# NAPaC.net
KiCad netlist of a schematic drawn in Altium Designer
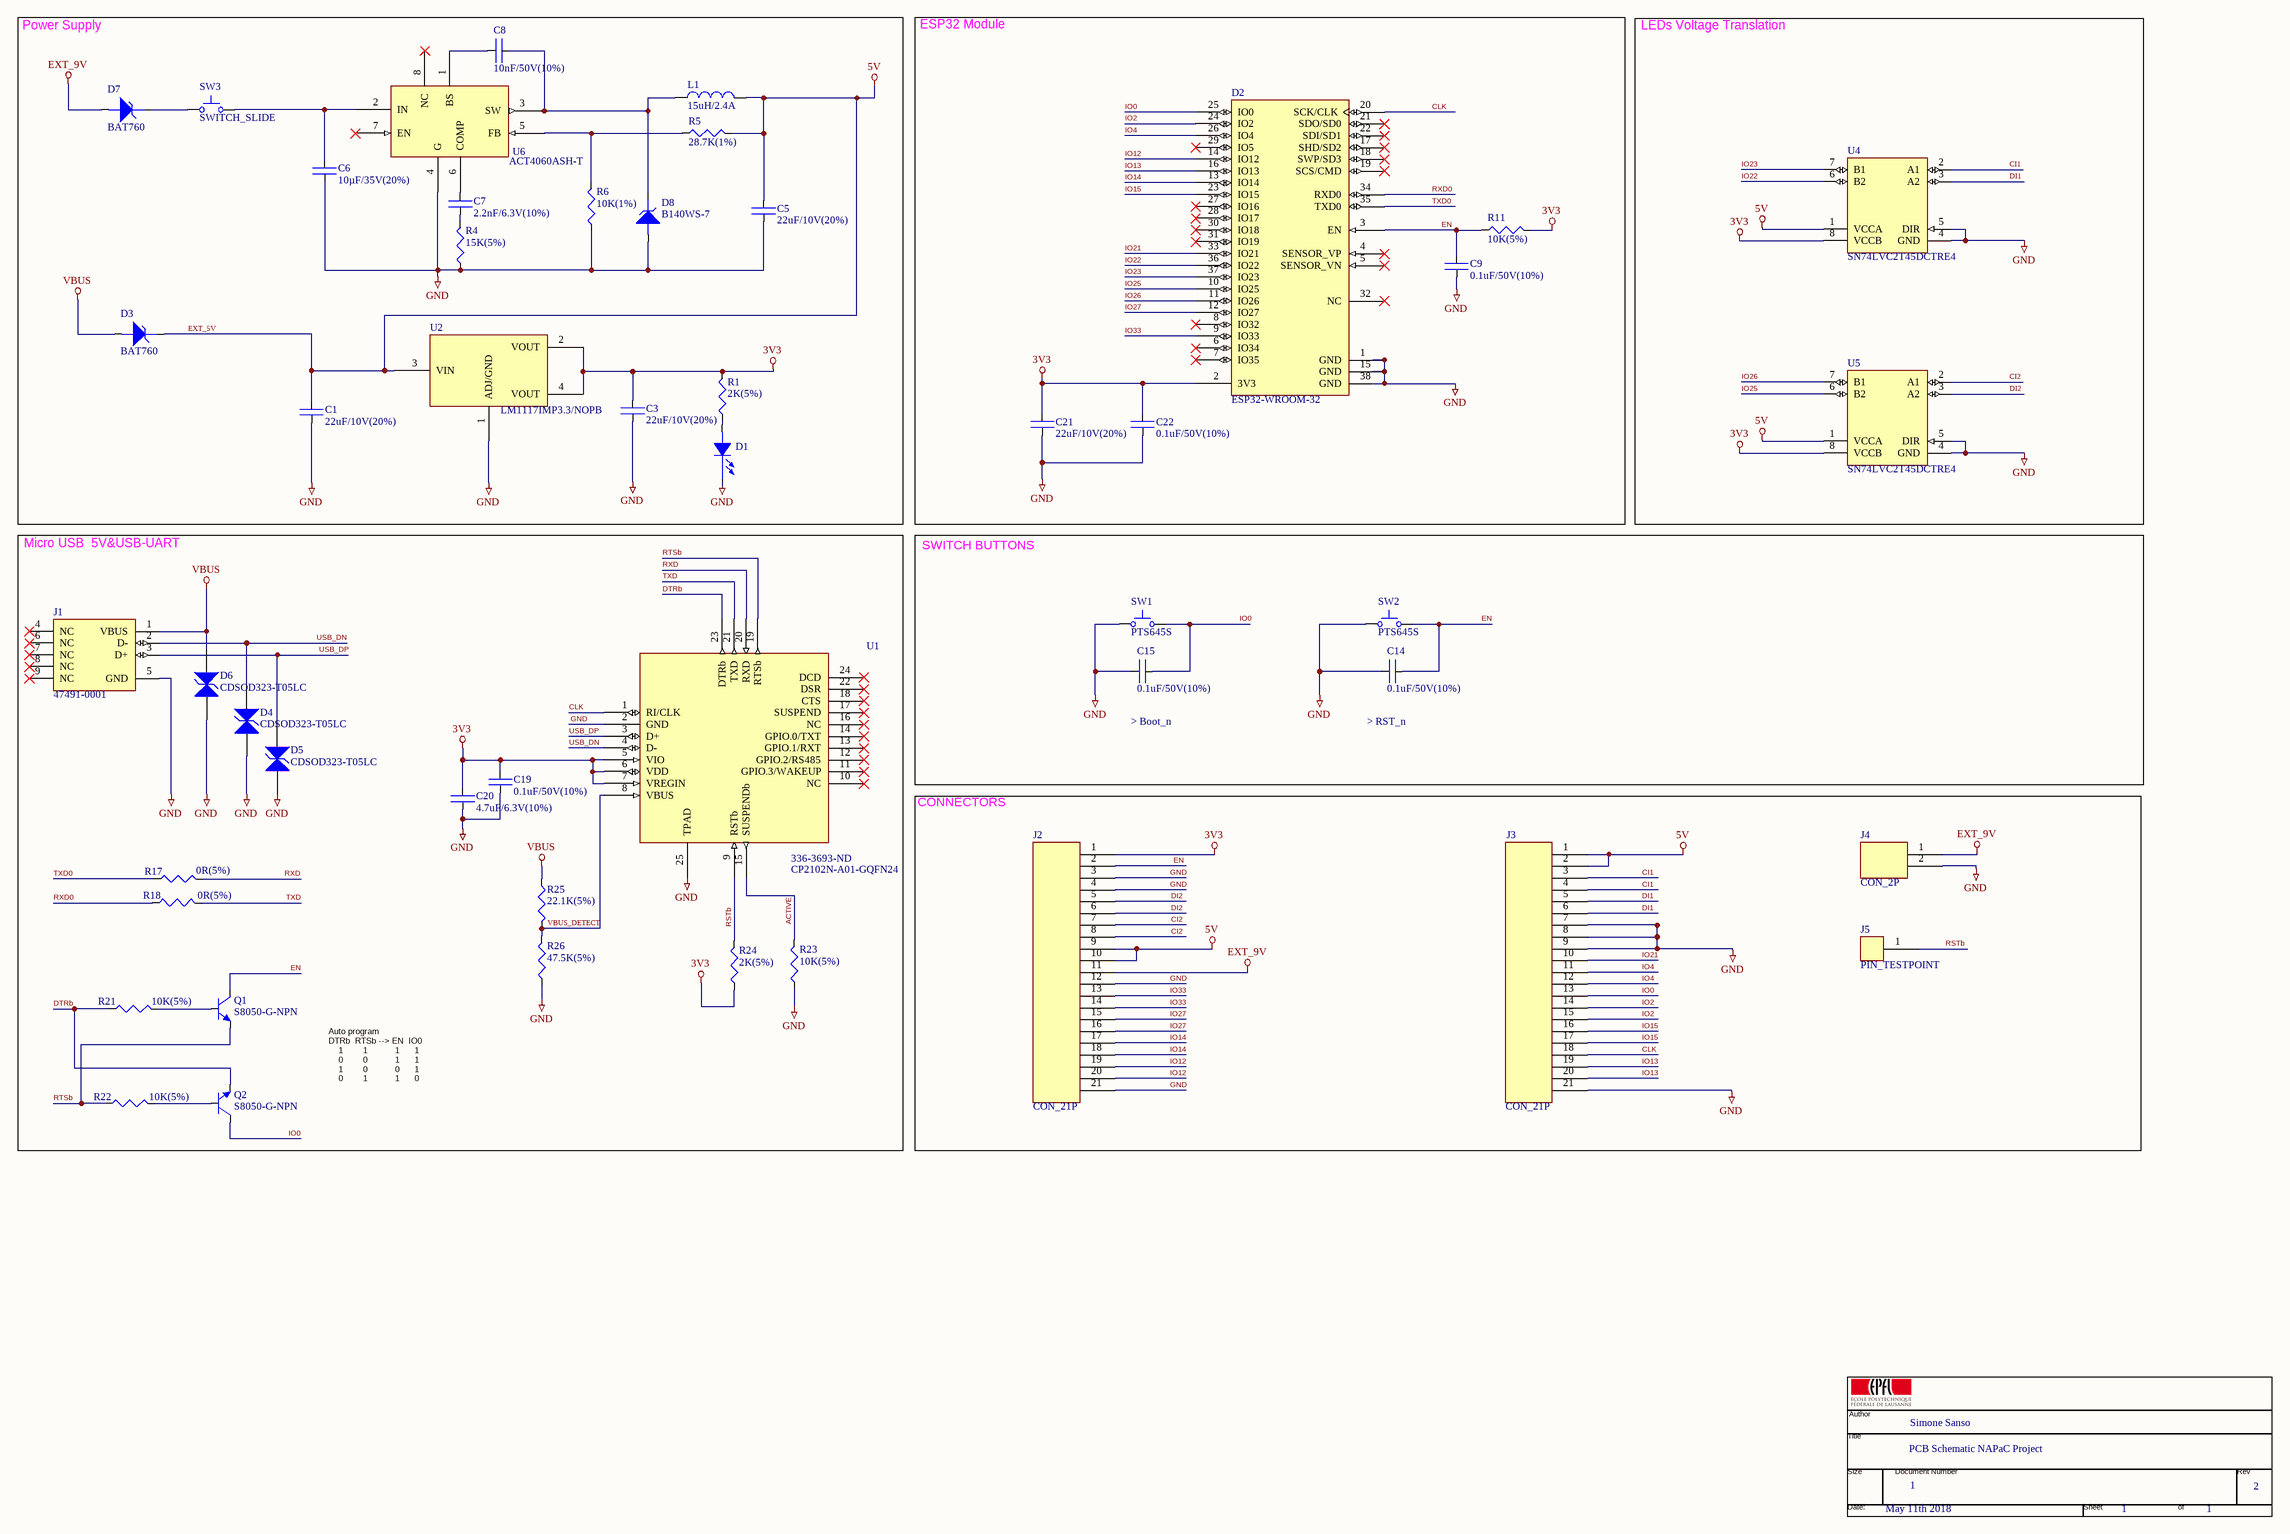
[diagram p0: NAPaC.SchDoc]

(export (version "E")
  (design (tool "Eeschema 10.0.6"))
  (components
    (comp (ref "*") (value "TITLE_BLOCK") (libsource (lib "NAPaC_Schlib") (part "TITLE_BLOCK")))
    (comp (ref "C1")
      (value "22uF/10V(20%)")
      (footprint "CAPC0603")
      (description "GRM188R61A226ME15D-22uF/10V(20%)")
      (libsource (lib "NAPaC_Schlib") (part "CAP-22uF/10V(20%)"))
    )
    (comp (ref "C3")
      (value "22uF/10V(20%)")
      (footprint "CAPC0603")
      (description "GRM188R61A226ME15D-22uF/10V(20%)")
      (libsource (lib "NAPaC_Schlib") (part "CAP-22uF/10V(20%)"))
    )
    (comp (ref "C5")
      (value "22uF/10V(20%)")
      (footprint "CAPC0603")
      (description "GRM188R61A226ME15D-22uF/10V(20%)")
      (libsource (lib "NAPaC_Schlib") (part "CAP-22uF/10V(20%)"))
    )
    (comp (ref "C6")
      (value "10µF/35V(20%)")
      (footprint "CAPC0603")
      (description "C0603C106M8PACTU")
      (libsource (lib "NAPaC_Schlib") (part "CAP-10µF/35V(20%)"))
    )
    (comp (ref "C7")
      (value "2.2nF/6.3V(10%)")
      (footprint "CAPC0603")
      (description "C0603X7R0J222K030BA")
      (libsource (lib "NAPaC_Schlib") (part "CAP-2.2nF/6.3V(10%)"))
    )
    (comp (ref "C8")
      (value "10nF/50V(10%)")
      (footprint "CAPC0603")
      (description "C1608X7R1H103K080AE")
      (libsource (lib "NAPaC_Schlib") (part "CAP-10nF/50V(10%)"))
    )
    (comp (ref "C9")
      (value "0.1uF/50V(10%)")
      (footprint "CAPC0603")
      (description "GRM188R71H104KA93D-0.1uF/50V(10%)")
      (libsource (lib "NAPaC_Schlib") (part "CAP-0.1uF/50V(10%)"))
    )
    (comp (ref "C14")
      (value "0.1uF/50V(10%)")
      (footprint "CAPC0603")
      (description "GRM188R71H104KA93D-0.1uF/50V(10%)")
      (libsource (lib "NAPaC_Schlib") (part "CAP-0.1uF/50V(10%)"))
    )
    (comp (ref "C15")
      (value "0.1uF/50V(10%)")
      (footprint "CAPC0603")
      (description "GRM188R71H104KA93D-0.1uF/50V(10%)")
      (libsource (lib "NAPaC_Schlib") (part "CAP-0.1uF/50V(10%)"))
    )
    (comp (ref "C19")
      (value "0.1uF/50V(10%)")
      (footprint "CAPC0603")
      (description "GRM188R71H104KA93D-0.1uF/50V(10%)")
      (libsource (lib "NAPaC_Schlib") (part "CAP-0.1uF/50V(10%)"))
    )
    (comp (ref "C20")
      (value "4.7uF/6.3V(10%)")
      (footprint "CAPC0603")
      (description "GRT188C80J475KE01D")
      (libsource (lib "NAPaC_Schlib") (part "CAP-0.4uF/6.3V(10%)"))
    )
    (comp (ref "C21")
      (value "22uF/10V(20%)")
      (footprint "CAPC0603")
      (description "GRM188R61A226ME15D-22uF/10V(20%)")
      (libsource (lib "NAPaC_Schlib") (part "CAP-22uF/10V(20%)"))
    )
    (comp (ref "C22")
      (value "0.1uF/50V(10%)")
      (footprint "CAPC0603")
      (description "GRM188R71H104KA93D-0.1uF/50V(10%)")
      (libsource (lib "NAPaC_Schlib") (part "CAP-0.1uF/50V(10%)"))
    )
    (comp (ref "D1")
      (value "SML-D12U1WT86")
      (footprint "SML-D12U1WT86")
      (description "SML-D12U1WT86-2.2V-20mA")
      (libsource (lib "NAPaC_Schlib") (part "RED_LED"))
    )
    (comp (ref "D2")
      (value "ESP32-WROOM-32")
      (footprint "OLMX-ESP-WROOM-32")
      (libsource (lib "NAPaC_Schlib") (part "ESP-WROOM-32"))
    )
    (comp (ref "D3")
      (value "BAT760")
      (footprint "SOD-323")
      (description "BAT760-7-Schottky Diodes & Rectifiers 0.5A 30V LF")
      (libsource (lib "NAPaC_Schlib") (part "SchottkyDiode"))
    )
    (comp (ref "D4")
      (value "CDSOD323-T05LC")
      (footprint "SOD-323")
      (libsource (lib "NAPaC_Schlib") (part "BidirectionalDiode"))
    )
    (comp (ref "D5")
      (value "CDSOD323-T05LC")
      (footprint "SOD-323")
      (libsource (lib "NAPaC_Schlib") (part "BidirectionalDiode"))
    )
    (comp (ref "D6")
      (value "CDSOD323-T05LC")
      (footprint "SOD-323")
      (libsource (lib "NAPaC_Schlib") (part "BidirectionalDiode"))
    )
    (comp (ref "D7")
      (value "BAT760")
      (footprint "SOD-323")
      (description "BAT760-7-Schottky Diodes & Rectifiers 0.5A 30V LF")
      (libsource (lib "NAPaC_Schlib") (part "SchottkyDiode"))
    )
    (comp (ref "D8")
      (value "B140WS-7")
      (footprint "SOD-323-SCHOTTKY_DIODE-40V/1A")
      (description "Diode Schottky 40V 1A 2-Pin SOD-323 T/R")
      (libsource (lib "NAPaC_Schlib") (part "SCHOTTKY_DIODE-40V/3A"))
    )
    (comp (ref "J1")
      (value "47491-0001")
      (footprint "USB-MICRO-B_V")
      (description "USB Connectors MICRO USB B RECPT MIDDLE MNT ASSY")
      (libsource (lib "NAPaC_Schlib") (part "USB_CON8"))
    )
    (comp (ref "J2")
      (value "CON_21P")
      (footprint "PINS_HEADER-21")
      (description "21 Positions Header, Breakaway Connector 0.100\" (2.54mm) Through Hole Tin")
      (libsource (lib "NAPaC_Schlib") (part "PINS_HEADER"))
    )
    (comp (ref "J3")
      (value "CON_21P")
      (footprint "PINS_HEADER-21")
      (description "21 Positions Header, Breakaway Connector 0.100\" (2.54mm) Through Hole Tin")
      (libsource (lib "NAPaC_Schlib") (part "PINS_HEADER"))
    )
    (comp (ref "J4")
      (value "CON_2P")
      (footprint "PINS_ALIM-2")
      (description "2 Positions Header, Breakaway Connector 0.100\" (2.54mm) Through Hole Tin")
      (libsource (lib "NAPaC_Schlib") (part "PIN_ALIM"))
    )
    (comp (ref "J5")
      (value "PIN_TESTPOINT")
      (footprint "PIN_TESTPOINT")
      (description "1 Position Header, Breakaway Connector 0.100\" (2.54mm) Through Hole Tin")
      (libsource (lib "NAPaC_Schlib") (part "PIN_TESTPOINT"))
    )
    (comp (ref "L1")
      (value "15uH/2.4A")
      (footprint "NRS8040-SELF-15uH/2.4A")
      (description "NRS8040T150MJGJ")
      (libsource (lib "NAPaC_Schlib") (part "SELF-15uH/2.4A"))
    )
    (comp (ref "Q1")
      (value "S8050-G-NPN")
      (footprint "SOT23")
      (description "750-SS8050-G-BJT NPN SOT-23-3 TRANSISTOR 1.5A 40V")
      (libsource (lib "NAPaC_Schlib") (part "SS8050-G-NPN"))
    )
    (comp (ref "Q2")
      (value "S8050-G-NPN")
      (description "750-SS8050-G-BJT NPN SOT-23-3 TRANSISTOR 1.5A 40V")
      (libsource (lib "NAPaC_Schlib") (part "SS8050-G-NPNbis"))
    )
    (comp (ref "R1")
      (value "2K(5%)")
      (footprint "RC0402")
      (description "RC0402JR-072KL")
      (libsource (lib "NAPaC_Schlib") (part "RESISTOR-2K(5%)"))
    )
    (comp (ref "R4")
      (value "15K(5%)")
      (footprint "RC0402")
      (description "RC0402JR-0715KL")
      (libsource (lib "NAPaC_Schlib") (part "RESISTOR-15K(5%)"))
    )
    (comp (ref "R5")
      (value "28.7K(1%)")
      (footprint "RC0402")
      (description "RC0402JR-072K7L")
      (libsource (lib "NAPaC_Schlib") (part "RESISTOR-28.7K(1%)"))
    )
    (comp (ref "R6")
      (value "10K(1%)")
      (footprint "RC0402")
      (description "RC0402F103CS")
      (libsource (lib "NAPaC_Schlib") (part "RESISTOR-10K(1%)"))
    )
    (comp (ref "R11")
      (value "10K(5%)")
      (footprint "RC0402")
      (description "RC0402JR-0710KL")
      (libsource (lib "NAPaC_Schlib") (part "RESISTOR-10K(5%)"))
    )
    (comp (ref "R17")
      (value "0R(5%)")
      (footprint "RC0402")
      (description "RC0402JR-070RL")
      (libsource (lib "NAPaC_Schlib") (part "RESISTOR-0R(5%)"))
    )
    (comp (ref "R18")
      (value "0R(5%)")
      (footprint "RC0402")
      (description "RC0402JR-070RL")
      (libsource (lib "NAPaC_Schlib") (part "RESISTOR-0R(5%)"))
    )
    (comp (ref "R21")
      (value "10K(5%)")
      (footprint "RC0402")
      (description "RC0402JR-0710KL")
      (libsource (lib "NAPaC_Schlib") (part "RESISTOR-10K(5%)"))
    )
    (comp (ref "R22")
      (value "10K(5%)")
      (footprint "RC0402")
      (description "RC0402JR-0710KL")
      (libsource (lib "NAPaC_Schlib") (part "RESISTOR-10K(5%)"))
    )
    (comp (ref "R23")
      (value "10K(5%)")
      (footprint "RC0402")
      (description "RC0402JR-0710KL")
      (libsource (lib "NAPaC_Schlib") (part "RESISTOR-10K(5%)"))
    )
    (comp (ref "R24")
      (value "2K(5%)")
      (footprint "RC0402")
      (description "RC0402JR-072KL")
      (libsource (lib "NAPaC_Schlib") (part "RESISTOR-2K(5%)"))
    )
    (comp (ref "R25")
      (value "22.1K(5%)")
      (footprint "RC0402")
      (description "RC0402FR-0722K1L")
      (libsource (lib "NAPaC_Schlib") (part "RESISTOR-22.1K(5%)"))
    )
    (comp (ref "R26")
      (value "47.5K(5%)")
      (footprint "RC0402")
      (description "RC0402FR-0747K5L")
      (libsource (lib "NAPaC_Schlib") (part "RESISTOR-47.5K(5%)"))
    )
    (comp (ref "SW1")
      (value "PTS645S")
      (footprint "CKCP-PTS645S_V")
      (description "PTS645SL432LFS")
      (libsource (lib "NAPaC_Schlib") (part "SW"))
    )
    (comp (ref "SW2")
      (value "PTS645S")
      (footprint "CKCP-PTS645S_V")
      (description "PTS645SL432LFS")
      (libsource (lib "NAPaC_Schlib") (part "SW"))
    )
    (comp (ref "SW3")
      (value "SWITCH_SLIDE")
      (footprint "SW_SLIDE")
      (description "48ASSP1S1M6QBT")
      (libsource (lib "NAPaC_Schlib") (part "SWITCH_SLIDE"))
    )
    (comp (ref "U1")
      (value "CP2102N-A01-GQFN24")
      (footprint "CP2102N-GQFN24")
      (fields (field (name "SUPPLIER PART NUMBER 1") "336-3693-ND"))
      (libsource (lib "NAPaC_Schlib") (part "CP2102N-GQFN24"))
    )
    (comp (ref "U2")
      (value "LM1117IMP3.3/NOPB")
      (footprint "LM1117")
      (libsource (lib "NAPaC_Schlib") (part "LM1117-3.3"))
    )
    (comp (ref "U4")
      (value "SN74LVC2T45DCTRE4")
      (footprint "VOLTAGE_TRANSLATOR_3.3-5V")
      (description "Translation - Voltage Levels DUAL-BIT DUAL SUPPLY TRANSCEIVER")
      (libsource (lib "NAPaC_Schlib") (part "VOLTAGE_TRANSLATOR_3.3-5V"))
    )
    (comp (ref "U5")
      (value "SN74LVC2T45DCTRE4")
      (footprint "VOLTAGE_TRANSLATOR_3.3-5V")
      (description "Translation - Voltage Levels DUAL-BIT DUAL SUPPLY TRANSCEIVER")
      (libsource (lib "NAPaC_Schlib") (part "VOLTAGE_TRANSLATOR_3.3-5V"))
    )
    (comp (ref "U6")
      (value "ACT4060ASH-T")
      (footprint "SWITCHING_VOLTAGE_REGULATOR")
      (libsource (lib "NAPaC_Schlib") (part "SWITCHING_VOLTAGE_REGULATOR"))
    )
  )
  (nets
    (net (code "1") (name "/ACTIVE") (class "Default")
      (node (ref "R23") (pin "2") (pinfunction "2_2") (pintype "passive"))
      (node (ref "U1") (pin "15") (pinfunction "SUSPENDb_15") (pintype "output"))
    )
    (net (code "2") (name "/CI1") (class "Default")
      (node (ref "J3") (pin "3") (pinfunction "1_3") (pintype "passive"))
      (node (ref "J3") (pin "4") (pinfunction "1_4") (pintype "passive"))
      (node (ref "U4") (pin "2") (pinfunction "A1_2") (pintype "bidirectional"))
    )
    (net (code "3") (name "/CI2") (class "Default")
      (node (ref "J2") (pin "7") (pinfunction "1_7") (pintype "passive"))
      (node (ref "J2") (pin "8") (pinfunction "1_8") (pintype "passive"))
      (node (ref "U5") (pin "2") (pinfunction "A1_2") (pintype "bidirectional"))
    )
    (net (code "4") (name "/CLK") (class "Default")
      (node (ref "D2") (pin "20") (pinfunction "SCK/CLK_20") (pintype "bidirectional"))
      (node (ref "J3") (pin "18") (pinfunction "1_18") (pintype "passive"))
      (node (ref "U1") (pin "1") (pinfunction "RI/CLK_1") (pintype "bidirectional"))
    )
    (net (code "5") (name "/DI1") (class "Default")
      (node (ref "J3") (pin "5") (pinfunction "1_5") (pintype "passive"))
      (node (ref "J3") (pin "6") (pinfunction "1_6") (pintype "passive"))
      (node (ref "U4") (pin "3") (pinfunction "A2_3") (pintype "bidirectional"))
    )
    (net (code "6") (name "/DI2") (class "Default")
      (node (ref "J2") (pin "5") (pinfunction "1_5") (pintype "passive"))
      (node (ref "J2") (pin "6") (pinfunction "1_6") (pintype "passive"))
      (node (ref "U5") (pin "3") (pinfunction "A2_3") (pintype "bidirectional"))
    )
    (net (code "7") (name "/DTRb") (class "Default")
      (node (ref "Q2") (pin "2") (pinfunction "EMITTER_2") (pintype "passive"))
      (node (ref "R21") (pin "1") (pinfunction "1_1") (pintype "passive"))
      (node (ref "U1") (pin "23") (pinfunction "DTRb_23") (pintype "output"))
    )
    (net (code "8") (name "/EN") (class "Default")
      (node (ref "C14") (pin "2") (pinfunction "2_2") (pintype "passive"))
      (node (ref "C9") (pin "2") (pinfunction "2_2") (pintype "passive"))
      (node (ref "D2") (pin "3") (pinfunction "EN_3") (pintype "input"))
      (node (ref "J2") (pin "2") (pinfunction "1_2") (pintype "passive"))
      (node (ref "Q1") (pin "3") (pinfunction "COLLECTOR_3") (pintype "passive"))
      (node (ref "R11") (pin "1") (pinfunction "1_1") (pintype "passive"))
      (node (ref "SW2") (pin "2") (pinfunction "2_2") (pintype "passive"))
    )
    (net (code "9") (name "/IO0") (class "Default")
      (node (ref "C15") (pin "2") (pinfunction "2_2") (pintype "passive"))
      (node (ref "D2") (pin "25") (pinfunction "IO0_25") (pintype "bidirectional"))
      (node (ref "J3") (pin "13") (pinfunction "1_13") (pintype "passive"))
      (node (ref "Q2") (pin "3") (pinfunction "COLLECTOR_3") (pintype "passive"))
      (node (ref "SW1") (pin "2") (pinfunction "2_2") (pintype "passive"))
    )
    (net (code "10") (name "/IO2") (class "Default")
      (node (ref "D2") (pin "24") (pinfunction "IO2_24") (pintype "bidirectional"))
      (node (ref "J3") (pin "14") (pinfunction "1_14") (pintype "passive"))
      (node (ref "J3") (pin "15") (pinfunction "1_15") (pintype "passive"))
    )
    (net (code "11") (name "/IO4") (class "Default")
      (node (ref "D2") (pin "26") (pinfunction "IO4_26") (pintype "bidirectional"))
      (node (ref "J3") (pin "11") (pinfunction "1_11") (pintype "passive"))
      (node (ref "J3") (pin "12") (pinfunction "1_12") (pintype "passive"))
    )
    (net (code "12") (name "/IO12") (class "Default")
      (node (ref "D2") (pin "14") (pinfunction "IO12_14") (pintype "bidirectional"))
      (node (ref "J2") (pin "19") (pinfunction "1_19") (pintype "passive"))
      (node (ref "J2") (pin "20") (pinfunction "1_20") (pintype "passive"))
    )
    (net (code "13") (name "/IO13") (class "Default")
      (node (ref "D2") (pin "16") (pinfunction "IO13_16") (pintype "bidirectional"))
      (node (ref "J3") (pin "19") (pinfunction "1_19") (pintype "passive"))
      (node (ref "J3") (pin "20") (pinfunction "1_20") (pintype "passive"))
    )
    (net (code "14") (name "/IO14") (class "Default")
      (node (ref "D2") (pin "13") (pinfunction "IO14_13") (pintype "bidirectional"))
      (node (ref "J2") (pin "17") (pinfunction "1_17") (pintype "passive"))
      (node (ref "J2") (pin "18") (pinfunction "1_18") (pintype "passive"))
    )
    (net (code "15") (name "/IO15") (class "Default")
      (node (ref "D2") (pin "23") (pinfunction "IO15_23") (pintype "bidirectional"))
      (node (ref "J3") (pin "16") (pinfunction "1_16") (pintype "passive"))
      (node (ref "J3") (pin "17") (pinfunction "1_17") (pintype "passive"))
    )
    (net (code "16") (name "/IO21") (class "Default")
      (node (ref "D2") (pin "33") (pinfunction "IO21_33") (pintype "bidirectional"))
      (node (ref "J3") (pin "10") (pinfunction "1_10") (pintype "passive"))
    )
    (net (code "17") (name "/IO22") (class "Default")
      (node (ref "D2") (pin "36") (pinfunction "IO22_36") (pintype "bidirectional"))
      (node (ref "U4") (pin "6") (pinfunction "B2_6") (pintype "bidirectional"))
    )
    (net (code "18") (name "/IO23") (class "Default")
      (node (ref "D2") (pin "37") (pinfunction "IO23_37") (pintype "bidirectional"))
      (node (ref "U4") (pin "7") (pinfunction "B1_7") (pintype "bidirectional"))
    )
    (net (code "19") (name "/IO25") (class "Default")
      (node (ref "D2") (pin "10") (pinfunction "IO25_10") (pintype "bidirectional"))
      (node (ref "U5") (pin "6") (pinfunction "B2_6") (pintype "bidirectional"))
    )
    (net (code "20") (name "/IO26") (class "Default")
      (node (ref "D2") (pin "11") (pinfunction "IO26_11") (pintype "bidirectional"))
      (node (ref "U5") (pin "7") (pinfunction "B1_7") (pintype "bidirectional"))
    )
    (net (code "21") (name "/IO27") (class "Default")
      (node (ref "D2") (pin "12") (pinfunction "IO27_12") (pintype "bidirectional"))
      (node (ref "J2") (pin "15") (pinfunction "1_15") (pintype "passive"))
      (node (ref "J2") (pin "16") (pinfunction "1_16") (pintype "passive"))
    )
    (net (code "22") (name "/IO33") (class "Default")
      (node (ref "D2") (pin "9") (pinfunction "IO33_9") (pintype "bidirectional"))
      (node (ref "J2") (pin "13") (pinfunction "1_13") (pintype "passive"))
      (node (ref "J2") (pin "14") (pinfunction "1_14") (pintype "passive"))
    )
    (net (code "23") (name "/RSTb") (class "Default")
      (node (ref "J5") (pin "1") (pinfunction "Testpoint_1") (pintype "passive"))
      (node (ref "R24") (pin "2") (pinfunction "2_2") (pintype "passive"))
      (node (ref "U1") (pin "9") (pinfunction "RSTb_9") (pintype "input"))
    )
    (net (code "24") (name "/RTSb") (class "Default")
      (node (ref "Q1") (pin "2") (pinfunction "EMITTER_2") (pintype "passive"))
      (node (ref "R22") (pin "1") (pinfunction "1_1") (pintype "passive"))
      (node (ref "U1") (pin "19") (pinfunction "RTSb_19") (pintype "output"))
    )
    (net (code "25") (name "/RXD") (class "Default")
      (node (ref "R17") (pin "2") (pinfunction "2_2") (pintype "passive"))
      (node (ref "U1") (pin "20") (pinfunction "RXD_20") (pintype "input"))
    )
    (net (code "26") (name "/RXD0") (class "Default")
      (node (ref "D2") (pin "34") (pinfunction "RXD0_34") (pintype "bidirectional"))
      (node (ref "R18") (pin "1") (pinfunction "1_1") (pintype "passive"))
    )
    (net (code "27") (name "/TXD") (class "Default")
      (node (ref "R18") (pin "2") (pinfunction "2_2") (pintype "passive"))
      (node (ref "U1") (pin "21") (pinfunction "TXD_21") (pintype "output"))
    )
    (net (code "28") (name "/TXD0") (class "Default")
      (node (ref "D2") (pin "35") (pinfunction "TXD0_35") (pintype "bidirectional"))
      (node (ref "R17") (pin "1") (pinfunction "1_1") (pintype "passive"))
    )
    (net (code "29") (name "/USB_DN") (class "Default")
      (node (ref "D4") (pin "2") (pinfunction "C_2") (pintype "passive"))
      (node (ref "J1") (pin "2") (pinfunction "D-_2") (pintype "bidirectional"))
      (node (ref "U1") (pin "4") (pinfunction "D-_4") (pintype "bidirectional"))
    )
    (net (code "30") (name "/USB_DP") (class "Default")
      (node (ref "D5") (pin "2") (pinfunction "C_2") (pintype "passive"))
      (node (ref "J1") (pin "3") (pinfunction "D+_3") (pintype "bidirectional"))
      (node (ref "U1") (pin "3") (pinfunction "D+_3") (pintype "bidirectional"))
    )
    (net (code "31") (name "/VBUS_DETECT") (class "Default")
      (node (ref "R25") (pin "2") (pinfunction "2_2") (pintype "passive"))
      (node (ref "R26") (pin "2") (pinfunction "2_2") (pintype "passive"))
      (node (ref "U1") (pin "8") (pinfunction "VBUS_8") (pintype "input"))
    )
    (net (code "32") (name "3V3") (class "Default")
      (node (ref "C19") (pin "2") (pinfunction "2_2") (pintype "passive"))
      (node (ref "C20") (pin "2") (pinfunction "2_2") (pintype "passive"))
      (node (ref "C21") (pin "2") (pinfunction "2_2") (pintype "passive"))
      (node (ref "C22") (pin "2") (pinfunction "2_2") (pintype "passive"))
      (node (ref "C3") (pin "2") (pinfunction "2_2") (pintype "passive"))
      (node (ref "D2") (pin "2") (pinfunction "3V3_2") (pintype "power_in"))
      (node (ref "J2") (pin "1") (pinfunction "1_1") (pintype "passive"))
      (node (ref "R1") (pin "2") (pinfunction "2_2") (pintype "passive"))
      (node (ref "R11") (pin "2") (pinfunction "2_2") (pintype "passive"))
      (node (ref "R24") (pin "1") (pinfunction "1_1") (pintype "passive"))
      (node (ref "U1") (pin "5") (pinfunction "VIO_5") (pintype "input"))
      (node (ref "U1") (pin "6") (pinfunction "VDD_6") (pintype "bidirectional"))
      (node (ref "U1") (pin "7") (pinfunction "VREGIN_7") (pintype "input"))
      (node (ref "U2") (pin "2") (pinfunction "VOUT_2") (pintype "power_in"))
      (node (ref "U2") (pin "4") (pinfunction "VOUT_4") (pintype "power_in"))
      (node (ref "U4") (pin "8") (pinfunction "VCCB_8") (pintype "power_in"))
      (node (ref "U5") (pin "8") (pinfunction "VCCB_8") (pintype "power_in"))
    )
    (net (code "33") (name "5V") (class "Default")
      (node (ref "C1") (pin "2") (pinfunction "2_2") (pintype "passive"))
      (node (ref "C5") (pin "2") (pinfunction "2_2") (pintype "passive"))
      (node (ref "D3") (pin "2") (pinfunction "K_2") (pintype "passive"))
      (node (ref "J2") (pin "10") (pinfunction "1_10") (pintype "passive"))
      (node (ref "J2") (pin "9") (pinfunction "1_9") (pintype "passive"))
      (node (ref "J3") (pin "1") (pinfunction "1_1") (pintype "passive"))
      (node (ref "J3") (pin "2") (pinfunction "1_2") (pintype "passive"))
      (node (ref "L1") (pin "2") (pinfunction "2_2") (pintype "passive"))
      (node (ref "R5") (pin "2") (pinfunction "2_2") (pintype "passive"))
      (node (ref "U2") (pin "3") (pinfunction "VIN_3") (pintype "power_in"))
      (node (ref "U4") (pin "1") (pinfunction "VCCA_1") (pintype "power_in"))
      (node (ref "U5") (pin "1") (pinfunction "VCCA_1") (pintype "power_in"))
    )
    (net (code "34") (name "EXT_9V") (class "Default")
      (node (ref "D7") (pin "1") (pinfunction "A_1") (pintype "passive"))
      (node (ref "J2") (pin "11") (pinfunction "1_11") (pintype "passive"))
      (node (ref "J4") (pin "1") (pinfunction "VIN_1") (pintype "power_in"))
    )
    (net (code "35") (name "GND") (class "Default")
      (node (ref "C1") (pin "1") (pinfunction "1_1") (pintype "passive"))
      (node (ref "C14") (pin "1") (pinfunction "1_1") (pintype "passive"))
      (node (ref "C15") (pin "1") (pinfunction "1_1") (pintype "passive"))
      (node (ref "C19") (pin "1") (pinfunction "1_1") (pintype "passive"))
      (node (ref "C20") (pin "1") (pinfunction "1_1") (pintype "passive"))
      (node (ref "C21") (pin "1") (pinfunction "1_1") (pintype "passive"))
      (node (ref "C22") (pin "1") (pinfunction "1_1") (pintype "passive"))
      (node (ref "C3") (pin "1") (pinfunction "1_1") (pintype "passive"))
      (node (ref "C5") (pin "1") (pinfunction "1_1") (pintype "passive"))
      (node (ref "C6") (pin "1") (pinfunction "1_1") (pintype "passive"))
      (node (ref "C9") (pin "1") (pinfunction "1_1") (pintype "passive"))
      (node (ref "D1") (pin "2") (pinfunction "2_2") (pintype "passive"))
      (node (ref "D2") (pin "1") (pinfunction "GND_1") (pintype "power_in"))
      (node (ref "D2") (pin "15") (pinfunction "GND_15") (pintype "power_in"))
      (node (ref "D2") (pin "38") (pinfunction "GND_38") (pintype "power_in"))
      (node (ref "D4") (pin "1") (pinfunction "C_1") (pintype "passive"))
      (node (ref "D5") (pin "1") (pinfunction "C_1") (pintype "passive"))
      (node (ref "D6") (pin "1") (pinfunction "C_1") (pintype "passive"))
      (node (ref "D8") (pin "1") (pinfunction "A_1") (pintype "passive"))
      (node (ref "J1") (pin "5") (pinfunction "GND_5") (pintype "power_in"))
      (node (ref "J2") (pin "12") (pinfunction "1_12") (pintype "passive"))
      (node (ref "J2") (pin "21") (pinfunction "1_21") (pintype "passive"))
      (node (ref "J2") (pin "3") (pinfunction "1_3") (pintype "passive"))
      (node (ref "J2") (pin "4") (pinfunction "1_4") (pintype "passive"))
      (node (ref "J3") (pin "21") (pinfunction "1_21") (pintype "passive"))
      (node (ref "J3") (pin "7") (pinfunction "1_7") (pintype "passive"))
      (node (ref "J3") (pin "8") (pinfunction "1_8") (pintype "passive"))
      (node (ref "J3") (pin "9") (pinfunction "1_9") (pintype "passive"))
      (node (ref "J4") (pin "2") (pinfunction "GND_2") (pintype "passive"))
      (node (ref "R23") (pin "1") (pinfunction "1_1") (pintype "passive"))
      (node (ref "R26") (pin "1") (pinfunction "1_1") (pintype "passive"))
      (node (ref "R4") (pin "1") (pinfunction "1_1") (pintype "passive"))
      (node (ref "R6") (pin "1") (pinfunction "1_1") (pintype "passive"))
      (node (ref "SW1") (pin "1") (pinfunction "1_1") (pintype "passive"))
      (node (ref "SW2") (pin "1") (pinfunction "1_1") (pintype "passive"))
      (node (ref "U1") (pin "2") (pinfunction "GND_2") (pintype "passive"))
      (node (ref "U1") (pin "25") (pinfunction "TPAD_25") (pintype "passive"))
      (node (ref "U2") (pin "1") (pinfunction "ADJ/GND_1") (pintype "passive"))
      (node (ref "U4") (pin "4") (pinfunction "GND_4") (pintype "power_in"))
      (node (ref "U4") (pin "5") (pinfunction "DIR_5") (pintype "input"))
      (node (ref "U5") (pin "4") (pinfunction "GND_4") (pintype "power_in"))
      (node (ref "U5") (pin "5") (pinfunction "DIR_5") (pintype "input"))
      (node (ref "U6") (pin "4") (pinfunction "G_4") (pintype "power_in"))
    )
    (net (code "36") (name "Net-(C7-Pad1)") (class "Default")
      (node (ref "C7") (pin "1") (pinfunction "1_1") (pintype "passive"))
      (node (ref "R4") (pin "2") (pinfunction "2_2") (pintype "passive"))
    )
    (net (code "37") (name "Net-(D1-Pad1)") (class "Default")
      (node (ref "D1") (pin "1") (pinfunction "1_1") (pintype "passive"))
      (node (ref "R1") (pin "1") (pinfunction "1_1") (pintype "passive"))
    )
    (net (code "38") (name "Net-(D7-K)") (class "Default")
      (node (ref "D7") (pin "2") (pinfunction "K_2") (pintype "passive"))
      (node (ref "SW3") (pin "1") (pinfunction "1_1") (pintype "passive"))
    )
    (net (code "39") (name "Net-(D8-K)") (class "Default")
      (node (ref "C8") (pin "2") (pinfunction "2_2") (pintype "passive"))
      (node (ref "D8") (pin "2") (pinfunction "K_2") (pintype "passive"))
      (node (ref "L1") (pin "1") (pinfunction "1_1") (pintype "passive"))
      (node (ref "U6") (pin "3") (pinfunction "SW_3") (pintype "output"))
    )
    (net (code "40") (name "Net-(Q1-BASE)") (class "Default")
      (node (ref "Q1") (pin "1") (pinfunction "BASE_1") (pintype "passive"))
      (node (ref "R21") (pin "2") (pinfunction "2_2") (pintype "passive"))
    )
    (net (code "41") (name "Net-(Q2-BASE)") (class "Default")
      (node (ref "Q2") (pin "1") (pinfunction "BASE_1") (pintype "passive"))
      (node (ref "R22") (pin "2") (pinfunction "2_2") (pintype "passive"))
    )
    (net (code "42") (name "Net-(U6-BS)") (class "Default")
      (node (ref "C8") (pin "1") (pinfunction "1_1") (pintype "passive"))
      (node (ref "U6") (pin "1") (pinfunction "BS_1") (pintype "passive"))
    )
    (net (code "43") (name "Net-(U6-COMP)") (class "Default")
      (node (ref "C7") (pin "2") (pinfunction "2_2") (pintype "passive"))
      (node (ref "U6") (pin "6") (pinfunction "COMP_6") (pintype "passive"))
    )
    (net (code "44") (name "Net-(U6-FB)") (class "Default")
      (node (ref "R5") (pin "1") (pinfunction "1_1") (pintype "passive"))
      (node (ref "R6") (pin "2") (pinfunction "2_2") (pintype "passive"))
      (node (ref "U6") (pin "5") (pinfunction "FB_5") (pintype "input"))
    )
    (net (code "45") (name "Net-(U6-IN)") (class "Default")
      (node (ref "C6") (pin "2") (pinfunction "2_2") (pintype "passive"))
      (node (ref "SW3") (pin "2") (pinfunction "2_2") (pintype "passive"))
      (node (ref "U6") (pin "2") (pinfunction "IN_2") (pintype "power_in"))
    )
    (net (code "46") (name "VBUS") (class "Default")
      (node (ref "D3") (pin "1") (pinfunction "A_1") (pintype "passive"))
      (node (ref "D6") (pin "2") (pinfunction "C_2") (pintype "passive"))
      (node (ref "J1") (pin "1") (pinfunction "VBUS_1") (pintype "power_in"))
      (node (ref "R25") (pin "1") (pinfunction "1_1") (pintype "passive"))
    )
    (net (code "47") (name "unconnected-(D2-IO5-Pad29)") (class "Default")
      (node (ref "D2") (pin "29") (pinfunction "IO5_29") (pintype "bidirectional+no_connect"))
    )
    (net (code "48") (name "unconnected-(D2-IO16-Pad27)") (class "Default")
      (node (ref "D2") (pin "27") (pinfunction "IO16_27") (pintype "bidirectional+no_connect"))
    )
    (net (code "49") (name "unconnected-(D2-IO17-Pad28)") (class "Default")
      (node (ref "D2") (pin "28") (pinfunction "IO17_28") (pintype "bidirectional+no_connect"))
    )
    (net (code "50") (name "unconnected-(D2-IO18-Pad30)") (class "Default")
      (node (ref "D2") (pin "30") (pinfunction "IO18_30") (pintype "bidirectional+no_connect"))
    )
    (net (code "51") (name "unconnected-(D2-IO19-Pad31)") (class "Default")
      (node (ref "D2") (pin "31") (pinfunction "IO19_31") (pintype "bidirectional+no_connect"))
    )
    (net (code "52") (name "unconnected-(D2-IO32-Pad8)") (class "Default")
      (node (ref "D2") (pin "8") (pinfunction "IO32_8") (pintype "bidirectional+no_connect"))
    )
    (net (code "53") (name "unconnected-(D2-IO34-Pad6)") (class "Default")
      (node (ref "D2") (pin "6") (pinfunction "IO34_6") (pintype "bidirectional+no_connect"))
    )
    (net (code "54") (name "unconnected-(D2-IO35-Pad7)") (class "Default")
      (node (ref "D2") (pin "7") (pinfunction "IO35_7") (pintype "bidirectional+no_connect"))
    )
    (net (code "55") (name "unconnected-(D2-NC-Pad32)") (class "Default")
      (node (ref "D2") (pin "32") (pinfunction "NC_32") (pintype "passive+no_connect"))
    )
    (net (code "56") (name "unconnected-(D2-SCS{slash}CMD-Pad19)") (class "Default")
      (node (ref "D2") (pin "19") (pinfunction "SCS/CMD_19") (pintype "bidirectional+no_connect"))
    )
    (net (code "57") (name "unconnected-(D2-SDI{slash}SD1-Pad22)") (class "Default")
      (node (ref "D2") (pin "22") (pinfunction "SDI/SD1_22") (pintype "bidirectional+no_connect"))
    )
    (net (code "58") (name "unconnected-(D2-SDO{slash}SD0-Pad21)") (class "Default")
      (node (ref "D2") (pin "21") (pinfunction "SDO/SD0_21") (pintype "bidirectional+no_connect"))
    )
    (net (code "59") (name "unconnected-(D2-SENSOR_VN-Pad5)") (class "Default")
      (node (ref "D2") (pin "5") (pinfunction "SENSOR_VN_5") (pintype "input+no_connect"))
    )
    (net (code "60") (name "unconnected-(D2-SENSOR_VP-Pad4)") (class "Default")
      (node (ref "D2") (pin "4") (pinfunction "SENSOR_VP_4") (pintype "input+no_connect"))
    )
    (net (code "61") (name "unconnected-(D2-SHD{slash}SD2-Pad17)") (class "Default")
      (node (ref "D2") (pin "17") (pinfunction "SHD/SD2_17") (pintype "bidirectional+no_connect"))
    )
    (net (code "62") (name "unconnected-(D2-SWP{slash}SD3-Pad18)") (class "Default")
      (node (ref "D2") (pin "18") (pinfunction "SWP/SD3_18") (pintype "bidirectional+no_connect"))
    )
    (net (code "63") (name "unconnected-(J1-NC-Pad4)") (class "Default")
      (node (ref "J1") (pin "4") (pinfunction "NC_4") (pintype "passive+no_connect"))
    )
    (net (code "64") (name "unconnected-(J1-NC-Pad6)") (class "Default")
      (node (ref "J1") (pin "6") (pinfunction "NC_6") (pintype "passive+no_connect"))
    )
    (net (code "65") (name "unconnected-(J1-NC-Pad7)") (class "Default")
      (node (ref "J1") (pin "7") (pinfunction "NC_7") (pintype "passive+no_connect"))
    )
    (net (code "66") (name "unconnected-(J1-NC-Pad8)") (class "Default")
      (node (ref "J1") (pin "8") (pinfunction "NC_8") (pintype "passive+no_connect"))
    )
    (net (code "67") (name "unconnected-(J1-NC-Pad9)") (class "Default")
      (node (ref "J1") (pin "9") (pinfunction "NC_9") (pintype "passive+no_connect"))
    )
    (net (code "68") (name "unconnected-(U1-CTS-Pad18)") (class "Default")
      (node (ref "U1") (pin "18") (pinfunction "CTS_18") (pintype "passive+no_connect"))
    )
    (net (code "69") (name "unconnected-(U1-DCD-Pad24)") (class "Default")
      (node (ref "U1") (pin "24") (pinfunction "DCD_24") (pintype "passive+no_connect"))
    )
    (net (code "70") (name "unconnected-(U1-DSR-Pad22)") (class "Default")
      (node (ref "U1") (pin "22") (pinfunction "DSR_22") (pintype "passive+no_connect"))
    )
    (net (code "71") (name "unconnected-(U1-GPIO.0{slash}TXT-Pad14)") (class "Default")
      (node (ref "U1") (pin "14") (pinfunction "GPIO.0/TXT_14") (pintype "passive+no_connect"))
    )
    (net (code "72") (name "unconnected-(U1-GPIO.1{slash}RXT-Pad13)") (class "Default")
      (node (ref "U1") (pin "13") (pinfunction "GPIO.1/RXT_13") (pintype "passive+no_connect"))
    )
    (net (code "73") (name "unconnected-(U1-GPIO.2{slash}RS485-Pad12)") (class "Default")
      (node (ref "U1") (pin "12") (pinfunction "GPIO.2/RS485_12") (pintype "passive+no_connect"))
    )
    (net (code "74") (name "unconnected-(U1-GPIO.3{slash}WAKEUP-Pad11)") (class "Default")
      (node (ref "U1") (pin "11") (pinfunction "GPIO.3/WAKEUP_11") (pintype "passive+no_connect"))
    )
    (net (code "75") (name "unconnected-(U1-NC-Pad10)") (class "Default")
      (node (ref "U1") (pin "10") (pinfunction "NC_10") (pintype "passive+no_connect"))
    )
    (net (code "76") (name "unconnected-(U1-NC-Pad16)") (class "Default")
      (node (ref "U1") (pin "16") (pinfunction "NC_16") (pintype "passive+no_connect"))
    )
    (net (code "77") (name "unconnected-(U1-SUSPEND-Pad17)") (class "Default")
      (node (ref "U1") (pin "17") (pinfunction "SUSPEND_17") (pintype "passive+no_connect"))
    )
    (net (code "78") (name "unconnected-(U6-EN-Pad7)") (class "Default")
      (node (ref "U6") (pin "7") (pinfunction "EN_7") (pintype "input+no_connect"))
    )
    (net (code "79") (name "unconnected-(U6-NC-Pad8)") (class "Default")
      (node (ref "U6") (pin "8") (pinfunction "NC_8") (pintype "passive+no_connect"))
    )
  )
)
